# cont.net
KiCad netlist of a schematic drawn in EAGLE
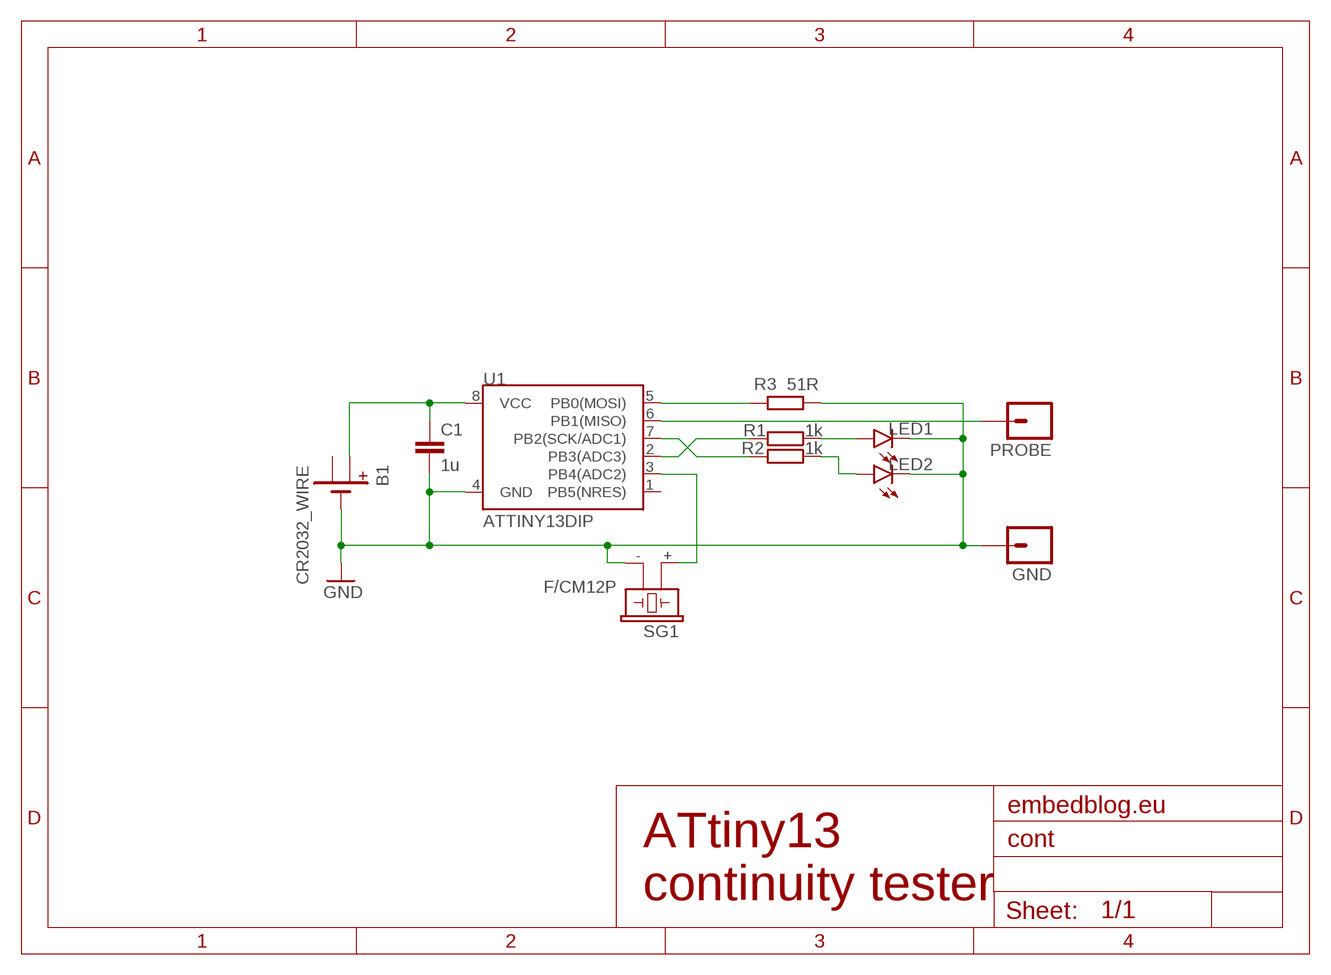
[diagram p0: schematic, sheet 1]

(export (version "E")
  (design (tool "Eeschema 10.0.6"))
  (components
    (comp (ref "B1")
      (value "CR2032_WIRE")
      (footprint "eagle-import:CR2032")
      (libsource (lib "eagle-import") (part "CR2032_WIRE"))
    )
    (comp (ref "C1")
      (value "1u")
      (footprint "eagle-import:C1206")
      (libsource (lib "eagle-import") (part "C-EUC1206"))
    )
    (comp (ref "GND")
      (value "M01OFFSET")
      (footprint "eagle-import:1X01_OFFSET")
      (libsource (lib "eagle-import") (part "M01OFFSET"))
    )
    (comp (ref "LED1")
      (value "LEDSML1206")
      (footprint "eagle-import:SML1206")
      (libsource (lib "eagle-import") (part "LEDSML1206"))
    )
    (comp (ref "LED2")
      (value "LEDSML1206")
      (footprint "eagle-import:SML1206")
      (libsource (lib "eagle-import") (part "LEDSML1206"))
    )
    (comp (ref "PROBE")
      (value "M01OFFSET")
      (footprint "eagle-import:1X01_OFFSET")
      (libsource (lib "eagle-import") (part "M01OFFSET"))
    )
    (comp (ref "R1")
      (value "1k")
      (footprint "eagle-import:R1206")
      (libsource (lib "eagle-import") (part "R-EU_R1206"))
    )
    (comp (ref "R2")
      (value "1k")
      (footprint "eagle-import:R1206")
      (libsource (lib "eagle-import") (part "R-EU_R1206"))
    )
    (comp (ref "R3")
      (value "51R")
      (footprint "eagle-import:R1206")
      (libsource (lib "eagle-import") (part "R-EU_R1206"))
    )
    (comp (ref "SG1")
      (value "F/CM12P")
      (footprint "eagle-import:F_CM12P")
      (libsource (lib "eagle-import") (part "F/CM12P"))
    )
    (comp (ref "U1")
      (value "ATTINY13DIP")
      (footprint "eagle-import:DIP08")
      (libsource (lib "eagle-import") (part "ATTINY13DIP"))
    )
  )
  (nets
    (net (code "1") (name "GND") (class "Default")
      (node (ref "B1") (pin "MINUS") (pinfunction "-_MINUS") (pintype "passive"))
      (node (ref "C1") (pin "2") (pinfunction "2_2") (pintype "passive"))
      (node (ref "GND") (pin "1") (pinfunction "1_1") (pintype "passive"))
      (node (ref "LED1") (pin "C") (pinfunction "C_C") (pintype "passive"))
      (node (ref "LED2") (pin "C") (pinfunction "C_C") (pintype "passive"))
      (node (ref "R3") (pin "1") (pinfunction "1_1") (pintype "passive"))
      (node (ref "SG1") (pin "-") (pinfunction "2_-") (pintype "passive"))
      (node (ref "U1") (pin "4") (pinfunction "GND_4") (pintype "bidirectional"))
    )
    (net (code "2") (name "Net-(B1-+1)") (class "Default")
      (node (ref "B1") (pin "PLUS1") (pinfunction "+1_PLUS1") (pintype "passive"))
      (node (ref "C1") (pin "1") (pinfunction "1_1") (pintype "passive"))
      (node (ref "U1") (pin "8") (pinfunction "VCC_8") (pintype "bidirectional"))
    )
    (net (code "3") (name "Net-(LED1-PadA)") (class "Default")
      (node (ref "LED1") (pin "A") (pinfunction "A_A") (pintype "passive"))
      (node (ref "R1") (pin "1") (pinfunction "1_1") (pintype "passive"))
    )
    (net (code "4") (name "Net-(LED2-PadA)") (class "Default")
      (node (ref "LED2") (pin "A") (pinfunction "A_A") (pintype "passive"))
      (node (ref "R2") (pin "1") (pinfunction "1_1") (pintype "passive"))
    )
    (net (code "5") (name "Net-(SG1-1)") (class "Default")
      (node (ref "SG1") (pin "+") (pinfunction "1_+") (pintype "passive"))
      (node (ref "U1") (pin "3") (pinfunction "PB4(ADC2)_3") (pintype "bidirectional"))
    )
    (net (code "6") (name "Net-(U1-PB0(MOSI))") (class "Default")
      (node (ref "R3") (pin "2") (pinfunction "2_2") (pintype "passive"))
      (node (ref "U1") (pin "5") (pinfunction "PB0(MOSI)_5") (pintype "bidirectional"))
    )
    (net (code "7") (name "Net-(U1-PB1(MISO))") (class "Default")
      (node (ref "PROBE") (pin "1") (pinfunction "1_1") (pintype "passive"))
      (node (ref "U1") (pin "6") (pinfunction "PB1(MISO)_6") (pintype "bidirectional"))
    )
    (net (code "8") (name "Net-(U1-PB2(SCK{slash}ADC1))") (class "Default")
      (node (ref "R2") (pin "2") (pinfunction "2_2") (pintype "passive"))
      (node (ref "U1") (pin "7") (pinfunction "PB2(SCK/ADC1)_7") (pintype "bidirectional"))
    )
    (net (code "9") (name "Net-(U1-PB3(ADC3))") (class "Default")
      (node (ref "R1") (pin "2") (pinfunction "2_2") (pintype "passive"))
      (node (ref "U1") (pin "2") (pinfunction "PB3(ADC3)_2") (pintype "bidirectional"))
    )
    (net (code "10") (name "unconnected-(B1-+2-PadPLUS2)") (class "Default")
      (node (ref "B1") (pin "PLUS2") (pinfunction "+2_PLUS2") (pintype "passive"))
    )
    (net (code "11") (name "unconnected-(U1-PB5(NRES)-Pad1)") (class "Default")
      (node (ref "U1") (pin "1") (pinfunction "PB5(NRES)_1") (pintype "bidirectional"))
    )
  )
)
